# Sheet2.net
KiCad netlist of a schematic drawn in Altium Designer
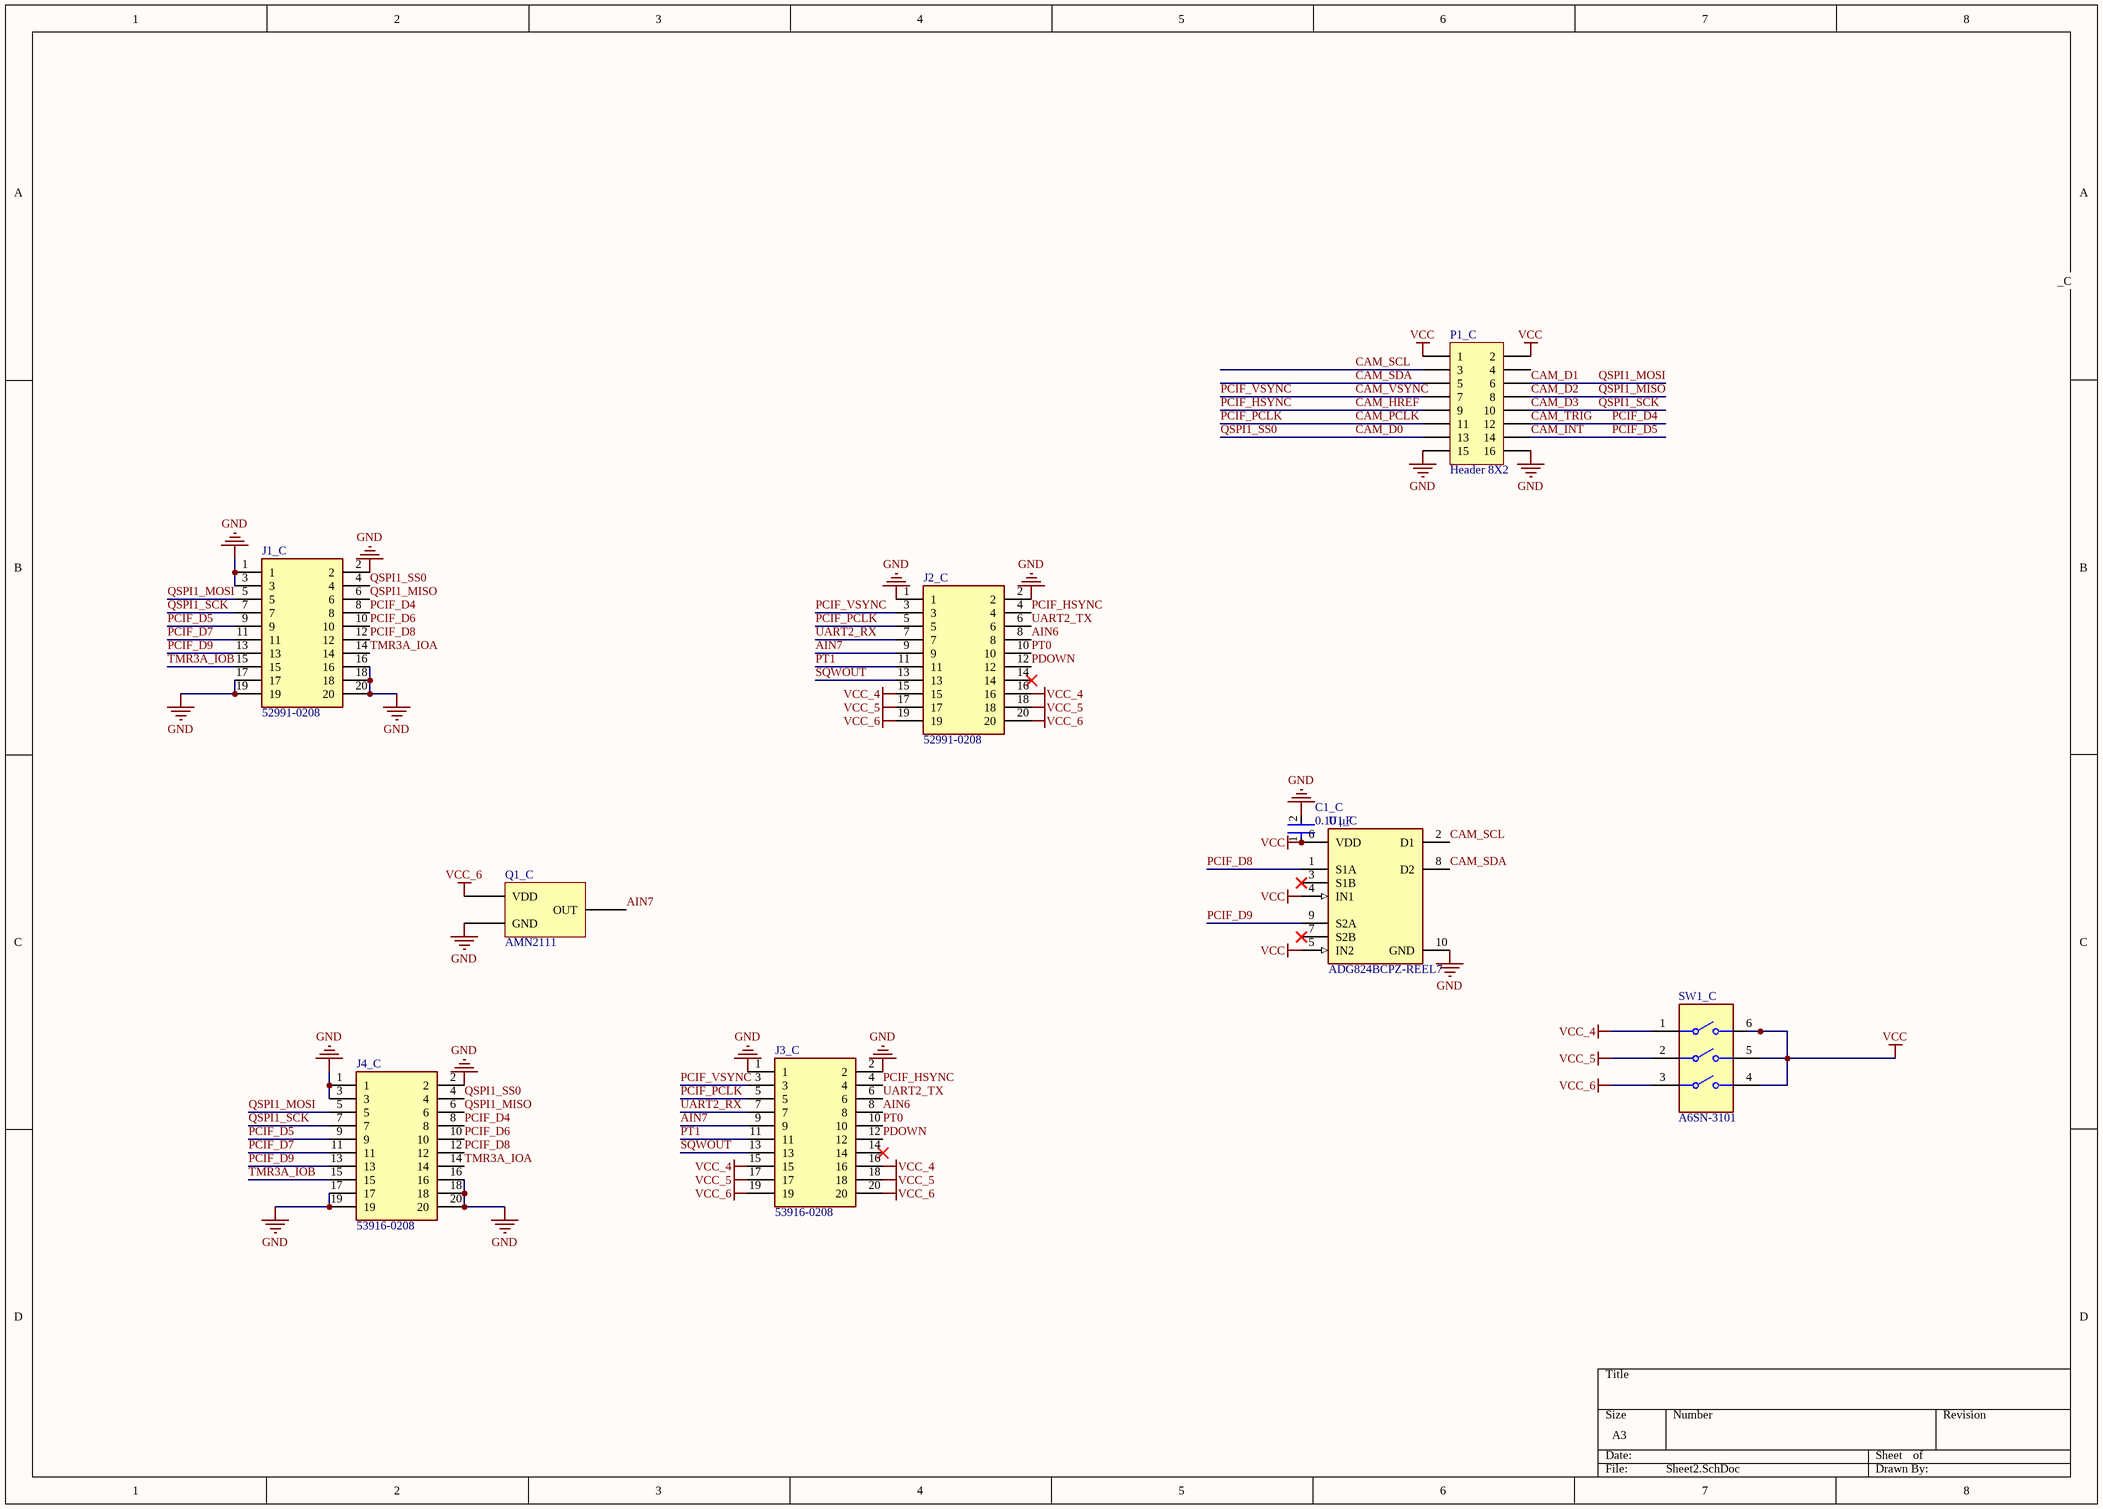
[diagram p0: Sheet2.SchDoc]

(export (version "E")
  (design (tool "Eeschema 10.0.6"))
  (components
    (comp (ref "C1_C")
      (value "C0402C104K8PACTU")
      (footprint "FP-C0402-BB-MFG")
      (description "CAP CER 0.1UF 10V X5R 0402")
      (fields
        (field (name "CAPACITANCE") "0.10 μF")
        (field (name "MANUFACTURER") "Kemet")
        (field (name "TOLERANCE") "0.1")
      )
      (libsource (lib "Altium Content Vault") (part "b4654b650e69147ec39a6b967a45e02"))
    )
    (comp (ref "J1_C")
      (value "52991-0208")
      (footprint "MOLEX_52991-0208")
      (description "20 Position Connector Receptacle, Center Strip Contacts Surface Mount Gold")
      (fields (field (name "MF") "Molex"))
      (libsource (lib "52991-0208") (part "52991-0208"))
    )
    (comp (ref "J2_C")
      (value "52991-0208")
      (footprint "MOLEX_52991-0208")
      (description "20 Position Connector Receptacle, Center Strip Contacts Surface Mount Gold")
      (fields (field (name "MF") "Molex"))
      (libsource (lib "52991-0208") (part "52991-0208"))
    )
    (comp (ref "J3_C")
      (value "53916-0208")
      (footprint "MOLEX-  539160208")
      (libsource (lib "52991-0208") (part "53916-0208"))
    )
    (comp (ref "J4_C")
      (value "53916-0208")
      (footprint "MOLEX-  539160208")
      (libsource (lib "52991-0208") (part "53916-0208"))
    )
    (comp (ref "P1_C")
      (value "Header 8X2")
      (footprint "HDR2X8")
      (description "Header, 8-Pin, Dual row")
      (fields (field (name "PUBLISHER") "Altium Limited"))
      (libsource (lib "Miscellaneous Connectors") (part "Header 8X2"))
    )
    (comp (ref "Q1_C")
      (value "AMN2111")
      (footprint "AMN21111")
      (libsource (lib "Integrated_Library1") (part "AMN2111"))
    )
    (comp (ref "SW1_C")
      (value "A6SN-3101")
      (footprint "FP-A6SN-3101-MFG")
      (description "DIP Switches / SIP Switches 3P Knife-Edge, 2.3mm Slide SMT Flat-Act")
      (fields (field (name "MANUFACTURER") "Omron Electronics Inc-EMC Div"))
      (libsource (lib "Altium Content Vault") (part "c5ed29025a0a80be921a75429a93ff4"))
    )
    (comp (ref "U1_C")
      (value "ADG824BCPZ-REEL7")
      (footprint "FP-CP-10-10-MFG")
      (description "IC SWITCH DUAL SPDT 10LFCSP")
      (fields
        (field (name "OCTOPART") "https://octopart.com/adg824bcpz-reel7-analog+devices-12410880")
        (field (name "MANUFACTURER") "Analog Devices")
      )
      (libsource (lib "Altium Content Vault") (part "750f7653eda72c1ba3820f182f788e1"))
    )
  )
  (nets
    (net (code "1") (name "/AIN6") (class "Default")
      (node (ref "J2_C") (pin "8") (pinfunction "8_8") (pintype "passive"))
      (node (ref "J3_C") (pin "8") (pinfunction "8_8") (pintype "passive"))
    )
    (net (code "2") (name "/AIN7") (class "Default")
      (node (ref "J2_C") (pin "9") (pinfunction "9_9") (pintype "passive"))
      (node (ref "J3_C") (pin "9") (pinfunction "9_9") (pintype "passive"))
      (node (ref "Q1_C") (pin "3") (pinfunction "OUT_3") (pintype "passive"))
    )
    (net (code "3") (name "/CAM_D0") (class "Default")
      (node (ref "J1_C") (pin "4") (pinfunction "4_4") (pintype "passive"))
      (node (ref "J4_C") (pin "4") (pinfunction "4_4") (pintype "passive"))
      (node (ref "P1_C") (pin "13") (pinfunction "13_13") (pintype "passive"))
    )
    (net (code "4") (name "/CAM_D1") (class "Default")
      (node (ref "J1_C") (pin "5") (pinfunction "5_5") (pintype "passive"))
      (node (ref "J4_C") (pin "5") (pinfunction "5_5") (pintype "passive"))
      (node (ref "P1_C") (pin "6") (pinfunction "6_6") (pintype "passive"))
    )
    (net (code "5") (name "/CAM_D2") (class "Default")
      (node (ref "J1_C") (pin "6") (pinfunction "6_6") (pintype "passive"))
      (node (ref "J4_C") (pin "6") (pinfunction "6_6") (pintype "passive"))
      (node (ref "P1_C") (pin "8") (pinfunction "8_8") (pintype "passive"))
    )
    (net (code "6") (name "/CAM_D3") (class "Default")
      (node (ref "J1_C") (pin "7") (pinfunction "7_7") (pintype "passive"))
      (node (ref "J4_C") (pin "7") (pinfunction "7_7") (pintype "passive"))
      (node (ref "P1_C") (pin "10") (pinfunction "10_10") (pintype "passive"))
    )
    (net (code "7") (name "/CAM_HREF") (class "Default")
      (node (ref "J2_C") (pin "4") (pinfunction "4_4") (pintype "passive"))
      (node (ref "J3_C") (pin "4") (pinfunction "4_4") (pintype "passive"))
      (node (ref "P1_C") (pin "9") (pinfunction "9_9") (pintype "passive"))
    )
    (net (code "8") (name "/CAM_INT") (class "Default")
      (node (ref "J1_C") (pin "9") (pinfunction "9_9") (pintype "passive"))
      (node (ref "J4_C") (pin "9") (pinfunction "9_9") (pintype "passive"))
      (node (ref "P1_C") (pin "14") (pinfunction "14_14") (pintype "passive"))
    )
    (net (code "9") (name "/CAM_PCLK") (class "Default")
      (node (ref "J2_C") (pin "5") (pinfunction "5_5") (pintype "passive"))
      (node (ref "J3_C") (pin "5") (pinfunction "5_5") (pintype "passive"))
      (node (ref "P1_C") (pin "11") (pinfunction "11_11") (pintype "passive"))
    )
    (net (code "10") (name "/CAM_SCL") (class "Default")
      (node (ref "P1_C") (pin "3") (pinfunction "3_3") (pintype "passive"))
      (node (ref "U1_C") (pin "2") (pinfunction "D1_2") (pintype "passive"))
    )
    (net (code "11") (name "/CAM_SDA") (class "Default")
      (node (ref "P1_C") (pin "5") (pinfunction "5_5") (pintype "passive"))
      (node (ref "U1_C") (pin "8") (pinfunction "D2_8") (pintype "passive"))
    )
    (net (code "12") (name "/CAM_TRIG") (class "Default")
      (node (ref "J1_C") (pin "8") (pinfunction "8_8") (pintype "passive"))
      (node (ref "J4_C") (pin "8") (pinfunction "8_8") (pintype "passive"))
      (node (ref "P1_C") (pin "12") (pinfunction "12_12") (pintype "passive"))
    )
    (net (code "13") (name "/CAM_VSYNC") (class "Default")
      (node (ref "J2_C") (pin "3") (pinfunction "3_3") (pintype "passive"))
      (node (ref "J3_C") (pin "3") (pinfunction "3_3") (pintype "passive"))
      (node (ref "P1_C") (pin "7") (pinfunction "7_7") (pintype "passive"))
    )
    (net (code "14") (name "/PCIF_D6") (class "Default")
      (node (ref "J1_C") (pin "10") (pinfunction "10_10") (pintype "passive"))
      (node (ref "J4_C") (pin "10") (pinfunction "10_10") (pintype "passive"))
    )
    (net (code "15") (name "/PCIF_D7") (class "Default")
      (node (ref "J1_C") (pin "11") (pinfunction "11_11") (pintype "passive"))
      (node (ref "J4_C") (pin "11") (pinfunction "11_11") (pintype "passive"))
    )
    (net (code "16") (name "/PCIF_D8") (class "Default")
      (node (ref "J1_C") (pin "12") (pinfunction "12_12") (pintype "passive"))
      (node (ref "J4_C") (pin "12") (pinfunction "12_12") (pintype "passive"))
      (node (ref "U1_C") (pin "1") (pinfunction "S1A_1") (pintype "passive"))
    )
    (net (code "17") (name "/PCIF_D9") (class "Default")
      (node (ref "J1_C") (pin "13") (pinfunction "13_13") (pintype "passive"))
      (node (ref "J4_C") (pin "13") (pinfunction "13_13") (pintype "passive"))
      (node (ref "U1_C") (pin "9") (pinfunction "S2A_9") (pintype "passive"))
    )
    (net (code "18") (name "/PDOWN") (class "Default")
      (node (ref "J2_C") (pin "12") (pinfunction "12_12") (pintype "passive"))
      (node (ref "J3_C") (pin "12") (pinfunction "12_12") (pintype "passive"))
    )
    (net (code "19") (name "/PT0") (class "Default")
      (node (ref "J2_C") (pin "10") (pinfunction "10_10") (pintype "passive"))
      (node (ref "J3_C") (pin "10") (pinfunction "10_10") (pintype "passive"))
    )
    (net (code "20") (name "/PT1") (class "Default")
      (node (ref "J2_C") (pin "11") (pinfunction "11_11") (pintype "passive"))
      (node (ref "J3_C") (pin "11") (pinfunction "11_11") (pintype "passive"))
    )
    (net (code "21") (name "/SQWOUT") (class "Default")
      (node (ref "J2_C") (pin "13") (pinfunction "13_13") (pintype "passive"))
      (node (ref "J3_C") (pin "13") (pinfunction "13_13") (pintype "passive"))
    )
    (net (code "22") (name "/TMR3A_IOA") (class "Default")
      (node (ref "J1_C") (pin "14") (pinfunction "14_14") (pintype "passive"))
      (node (ref "J4_C") (pin "14") (pinfunction "14_14") (pintype "passive"))
    )
    (net (code "23") (name "/TMR3A_IOB") (class "Default")
      (node (ref "J1_C") (pin "15") (pinfunction "15_15") (pintype "passive"))
      (node (ref "J4_C") (pin "15") (pinfunction "15_15") (pintype "passive"))
    )
    (net (code "24") (name "/UART2_RX") (class "Default")
      (node (ref "J2_C") (pin "7") (pinfunction "7_7") (pintype "passive"))
      (node (ref "J3_C") (pin "7") (pinfunction "7_7") (pintype "passive"))
    )
    (net (code "25") (name "/UART2_TX") (class "Default")
      (node (ref "J2_C") (pin "6") (pinfunction "6_6") (pintype "passive"))
      (node (ref "J3_C") (pin "6") (pinfunction "6_6") (pintype "passive"))
    )
    (net (code "26") (name "GND") (class "Default")
      (node (ref "C1_C") (pin "2") (pinfunction "2_2") (pintype "passive"))
      (node (ref "J1_C") (pin "1") (pinfunction "1_1") (pintype "passive"))
      (node (ref "J1_C") (pin "16") (pinfunction "16_16") (pintype "passive"))
      (node (ref "J1_C") (pin "17") (pinfunction "17_17") (pintype "passive"))
      (node (ref "J1_C") (pin "18") (pinfunction "18_18") (pintype "passive"))
      (node (ref "J1_C") (pin "19") (pinfunction "19_19") (pintype "passive"))
      (node (ref "J1_C") (pin "2") (pinfunction "2_2") (pintype "passive"))
      (node (ref "J1_C") (pin "20") (pinfunction "20_20") (pintype "passive"))
      (node (ref "J1_C") (pin "3") (pinfunction "3_3") (pintype "passive"))
      (node (ref "J2_C") (pin "1") (pinfunction "1_1") (pintype "passive"))
      (node (ref "J2_C") (pin "2") (pinfunction "2_2") (pintype "passive"))
      (node (ref "J3_C") (pin "1") (pinfunction "1_1") (pintype "passive"))
      (node (ref "J3_C") (pin "2") (pinfunction "2_2") (pintype "passive"))
      (node (ref "J4_C") (pin "1") (pinfunction "1_1") (pintype "passive"))
      (node (ref "J4_C") (pin "16") (pinfunction "16_16") (pintype "passive"))
      (node (ref "J4_C") (pin "17") (pinfunction "17_17") (pintype "passive"))
      (node (ref "J4_C") (pin "18") (pinfunction "18_18") (pintype "passive"))
      (node (ref "J4_C") (pin "19") (pinfunction "19_19") (pintype "passive"))
      (node (ref "J4_C") (pin "2") (pinfunction "2_2") (pintype "passive"))
      (node (ref "J4_C") (pin "20") (pinfunction "20_20") (pintype "passive"))
      (node (ref "J4_C") (pin "3") (pinfunction "3_3") (pintype "passive"))
      (node (ref "P1_C") (pin "15") (pinfunction "15_15") (pintype "passive"))
      (node (ref "P1_C") (pin "16") (pinfunction "16_16") (pintype "passive"))
      (node (ref "Q1_C") (pin "2") (pinfunction "GND_2") (pintype "passive"))
      (node (ref "U1_C") (pin "10") (pinfunction "GND_10") (pintype "power_in"))
    )
    (net (code "27") (name "VCC") (class "Default")
      (node (ref "C1_C") (pin "1") (pinfunction "1_1") (pintype "passive"))
      (node (ref "P1_C") (pin "1") (pinfunction "1_1") (pintype "passive"))
      (node (ref "P1_C") (pin "2") (pinfunction "2_2") (pintype "passive"))
      (node (ref "SW1_C") (pin "4") (pinfunction "4_4") (pintype "passive"))
      (node (ref "SW1_C") (pin "5") (pinfunction "5_5") (pintype "passive"))
      (node (ref "SW1_C") (pin "6") (pinfunction "6_6") (pintype "passive"))
      (node (ref "U1_C") (pin "4") (pinfunction "IN1_4") (pintype "input"))
      (node (ref "U1_C") (pin "5") (pinfunction "IN2_5") (pintype "input"))
      (node (ref "U1_C") (pin "6") (pinfunction "VDD_6") (pintype "power_in"))
    )
    (net (code "28") (name "VCC_4") (class "Default")
      (node (ref "J2_C") (pin "15") (pinfunction "15_15") (pintype "passive"))
      (node (ref "J2_C") (pin "16") (pinfunction "16_16") (pintype "passive"))
      (node (ref "J3_C") (pin "15") (pinfunction "15_15") (pintype "passive"))
      (node (ref "J3_C") (pin "16") (pinfunction "16_16") (pintype "passive"))
      (node (ref "SW1_C") (pin "1") (pinfunction "1_1") (pintype "passive"))
    )
    (net (code "29") (name "VCC_5") (class "Default")
      (node (ref "J2_C") (pin "17") (pinfunction "17_17") (pintype "passive"))
      (node (ref "J2_C") (pin "18") (pinfunction "18_18") (pintype "passive"))
      (node (ref "J3_C") (pin "17") (pinfunction "17_17") (pintype "passive"))
      (node (ref "J3_C") (pin "18") (pinfunction "18_18") (pintype "passive"))
      (node (ref "SW1_C") (pin "2") (pinfunction "2_2") (pintype "passive"))
    )
    (net (code "30") (name "VCC_6") (class "Default")
      (node (ref "J2_C") (pin "19") (pinfunction "19_19") (pintype "passive"))
      (node (ref "J2_C") (pin "20") (pinfunction "20_20") (pintype "passive"))
      (node (ref "J3_C") (pin "19") (pinfunction "19_19") (pintype "passive"))
      (node (ref "J3_C") (pin "20") (pinfunction "20_20") (pintype "passive"))
      (node (ref "Q1_C") (pin "1") (pinfunction "VDD_1") (pintype "passive"))
      (node (ref "SW1_C") (pin "3") (pinfunction "3_3") (pintype "passive"))
    )
    (net (code "31") (name "unconnected-(J2_C-Pad14)") (class "Default")
      (node (ref "J2_C") (pin "14") (pinfunction "14_14") (pintype "passive+no_connect"))
    )
    (net (code "32") (name "unconnected-(J3_C-Pad14)") (class "Default")
      (node (ref "J3_C") (pin "14") (pinfunction "14_14") (pintype "passive+no_connect"))
    )
    (net (code "33") (name "unconnected-(P1_C-Pad4)") (class "Default")
      (node (ref "P1_C") (pin "4") (pinfunction "4_4") (pintype "passive"))
    )
    (net (code "34") (name "unconnected-(U1_C-S1B-Pad3)") (class "Default")
      (node (ref "U1_C") (pin "3") (pinfunction "S1B_3") (pintype "passive+no_connect"))
    )
    (net (code "35") (name "unconnected-(U1_C-S2B-Pad7)") (class "Default")
      (node (ref "U1_C") (pin "7") (pinfunction "S2B_7") (pintype "passive+no_connect"))
    )
  )
)
